# Pg14_FPGA_DDR3.net
KiCad netlist of a schematic drawn in Altium Designer
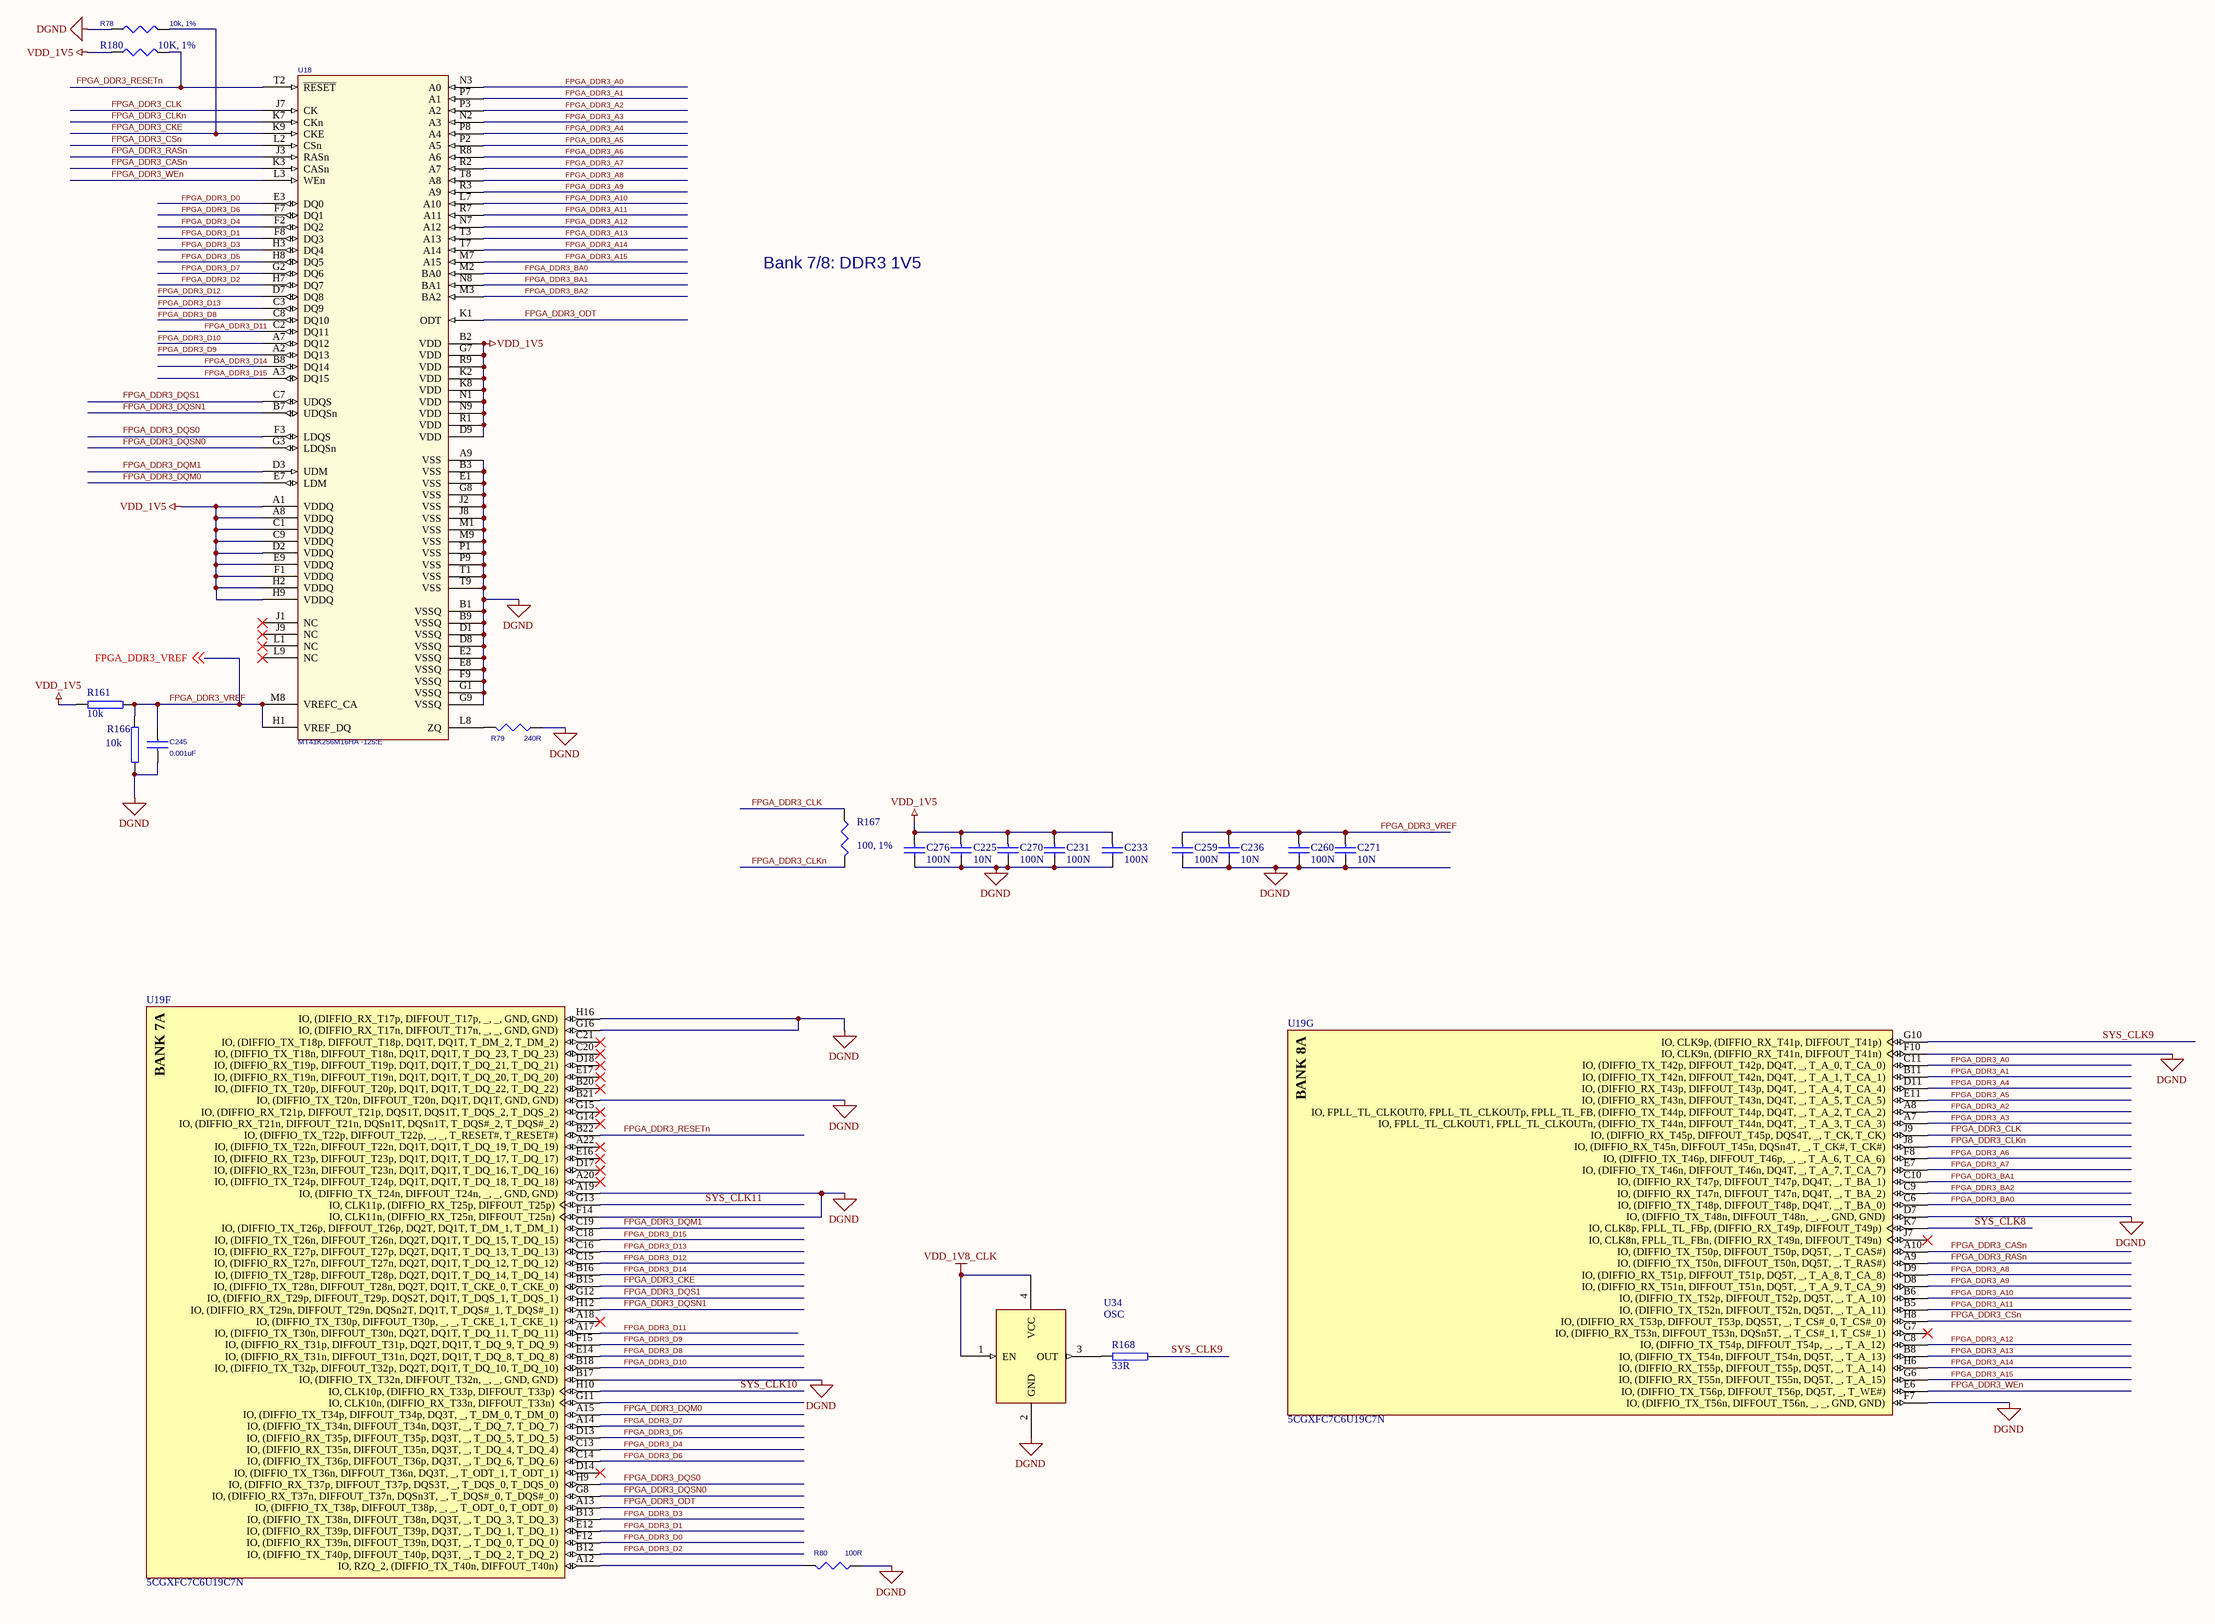
[diagram p0: Pg14_FPGA_DDR3.SchDoc]

(export (version "E")
  (design (tool "Eeschema 10.0.6"))
  (components
    (comp (ref "C225")
      (value "10N")
      (footprint "sc0402")
      (description "NON-POLARISED CAP")
      (libsource (lib "Fireflash_B") (part "CAP"))
    )
    (comp (ref "C231")
      (value "100N")
      (footprint "sc0402")
      (description "NON-POLARISED CAP")
      (libsource (lib "Fireflash_B") (part "CAP"))
    )
    (comp (ref "C233")
      (value "100N")
      (footprint "sc0402")
      (description "NON-POLARISED CAP")
      (libsource (lib "Fireflash_B") (part "CAP"))
    )
    (comp (ref "C236")
      (value "10N")
      (footprint "sc0402")
      (description "NON-POLARISED CAP")
      (libsource (lib "Fireflash_B") (part "CAP"))
    )
    (comp (ref "C245")
      (value "0.001uF")
      (footprint "SM-7351-CAP-0402")
      (fields (field (name "MFR") "AVX") (field (name "TIINTPARTNUMBER") "1C0093"))
      (libsource (lib "*") (part "0.001uFCapacitor50V5%0402"))
    )
    (comp (ref "C259")
      (value "100N")
      (footprint "sc0402")
      (description "NON-POLARISED CAP")
      (libsource (lib "Fireflash_B") (part "CAP"))
    )
    (comp (ref "C260")
      (value "100N")
      (footprint "0603")
      (description "NON-POLARISED CAP")
      (libsource (lib "Fireflash_B") (part "CAP"))
    )
    (comp (ref "C270")
      (value "100N")
      (footprint "sc0402")
      (description "NON-POLARISED CAP")
      (libsource (lib "Fireflash_B") (part "CAP"))
    )
    (comp (ref "C271")
      (value "10N")
      (footprint "sc0402")
      (description "NON-POLARISED CAP")
      (libsource (lib "Fireflash_B") (part "CAP"))
    )
    (comp (ref "C276")
      (value "100N")
      (footprint "sc0402")
      (description "NON-POLARISED CAP")
      (libsource (lib "Fireflash_B") (part "CAP"))
    )
    (comp (ref "R78")
      (value "10k, 1%")
      (footprint "sm-7351-res-0402 - duplicate")
      (description "RES 10K OHM 1/16W 5% 0402 SMD")
      (fields
        (field (name "MANUFACTURER") "Rohm Semiconductor")
        (field (name "MANUFACTURER PART NUMBER") "MCR01MZPJ103")
      )
      (libsource (lib "BEAGLEBONEBLACK_REV A5B") (part "RES_10K_1/16W_1%_0402"))
    )
    (comp (ref "R79")
      (value "240R")
      (footprint "SM-7351-RES-0402")
      (description "Resistor 10Kohm 1/16W 5% 0402")
      (fields (field (name "MFR") "Rohm") (field (name "TIINTPARTNUMBER") "1R0168"))
      (libsource (lib "*") (part "10KOhmResistor1/16W0402"))
    )
    (comp (ref "R80")
      (value "100R")
      (footprint "SM-7351-RES-0402")
      (description "Resistor 10Kohm 1/16W 5% 0402")
      (fields (field (name "MFR") "Rohm") (field (name "TIINTPARTNUMBER") "1R0168"))
      (libsource (lib "*") (part "10KOhmResistor1/16W0402"))
    )
    (comp (ref "R161")
      (value "10k")
      (footprint "0603")
      (description "RESISTOR")
      (libsource (lib "Fireflash_B") (part "RES"))
    )
    (comp (ref "R166")
      (value "10k")
      (footprint "0603")
      (description "RESISTOR")
      (libsource (lib "Fireflash_B") (part "RES"))
    )
    (comp (ref "R167")
      (value "100, 1%")
      (footprint "sc0402")
      (libsource (lib "BEAGLE_C2A_Library") (part "RESISTOR"))
    )
    (comp (ref "R168")
      (value "33R")
      (footprint "sc0402")
      (description "Resistor")
      (libsource (lib "Ibis4") (part "RES"))
    )
    (comp (ref "R180")
      (value "10K, 1%")
      (footprint "sc0402")
      (description "RES 1.50K OHM 1/16W 1% 0402 SMD")
      (fields
        (field (name "MANUFACTURER") "Yageo")
        (field (name "MANUFACTURER PART NUMBER") "RC0402FR-071K5L")
      )
      (libsource (lib "BEAGLEBONEBLACK_REV A5B") (part "RES_10K_1/16W_1%_0402"))
    )
    (comp (ref "U18")
      (value "MT41K256M16HA -125:E")
      (footprint "BGA14X10-96")
      (description "DDR2 SDRAM 2Gb (256Mx8)")
      (fields
        (field (name "MANUFACTURER") "Micron Technology")
        (field (name "MANUFACTURER PART NUMBER") "MT41K256M16HA-125:E")
      )
      (libsource (lib "BEAGLEBONEBLACK_REV A5B") (part "MT41K256M16HA"))
    )
    (comp (ref "U19")
      (value "5CGXFC7C6U19C7N")
      (footprint "ALTR-UBGA484_A-190")
      (fields (field (name "MANUFACTURER") "Altera"))
      (libsource (lib "Altera Cyclone V") (part "5CGXFC7C6U19C7N"))
    )
    (comp (ref "U34")
      (value "OSC")
      (footprint "Osc 3.2x2.5")
      (description "XTAL OSCILLATOR MODULE")
      (libsource (lib "Fireflash_B") (part "OSC"))
    )
  )
  (nets
    (net (code "1") (name "/FPGA_DDR3_A0") (class "Default")
      (node (ref "U18") (pin "N3") (pinfunction "A0_N3") (pintype "input"))
      (node (ref "U19") (pin "C11") (pinfunction "IO,_(DIFFIO_TX_T42p,_DIFFOUT_T42p,_DQ4T,__,_T_A_0,_T_CA_0)_C11") (pintype "bidirectional"))
    )
    (net (code "2") (name "/FPGA_DDR3_A1") (class "Default")
      (node (ref "U18") (pin "P7") (pinfunction "A1_P7") (pintype "input"))
      (node (ref "U19") (pin "B11") (pinfunction "IO,_(DIFFIO_TX_T42n,_DIFFOUT_T42n,_DQ4T,__,_T_A_1,_T_CA_1)_B11") (pintype "bidirectional"))
    )
    (net (code "3") (name "/FPGA_DDR3_A2") (class "Default")
      (node (ref "U18") (pin "P3") (pinfunction "A2_P3") (pintype "input"))
      (node (ref "U19") (pin "A8") (pinfunction "IO,_FPLL_TL_CLKOUT0,_FPLL_TL_CLKOUTp,_FPLL_TL_FB,_(DIFFIO_TX_T44p,_DIFFOUT_T44p,_DQ4T,__,_T_A_2,_T_CA_2)_A8") (pintype "bidirectional"))
    )
    (net (code "4") (name "/FPGA_DDR3_A3") (class "Default")
      (node (ref "U18") (pin "N2") (pinfunction "A3_N2") (pintype "input"))
      (node (ref "U19") (pin "A7") (pinfunction "IO,_FPLL_TL_CLKOUT1,_FPLL_TL_CLKOUTn,_(DIFFIO_TX_T44n,_DIFFOUT_T44n,_DQ4T,__,_T_A_3,_T_CA_3)_A7") (pintype "bidirectional"))
    )
    (net (code "5") (name "/FPGA_DDR3_A4") (class "Default")
      (node (ref "U18") (pin "P8") (pinfunction "A4_P8") (pintype "input"))
      (node (ref "U19") (pin "D11") (pinfunction "IO,_(DIFFIO_RX_T43p,_DIFFOUT_T43p,_DQ4T,__,_T_A_4,_T_CA_4)_D11") (pintype "bidirectional"))
    )
    (net (code "6") (name "/FPGA_DDR3_A5") (class "Default")
      (node (ref "U18") (pin "P2") (pinfunction "A5_P2") (pintype "input"))
      (node (ref "U19") (pin "E11") (pinfunction "IO,_(DIFFIO_RX_T43n,_DIFFOUT_T43n,_DQ4T,__,_T_A_5,_T_CA_5)_E11") (pintype "bidirectional"))
    )
    (net (code "7") (name "/FPGA_DDR3_A6") (class "Default")
      (node (ref "U18") (pin "R8") (pinfunction "A6_R8") (pintype "input"))
      (node (ref "U19") (pin "F8") (pinfunction "IO,_(DIFFIO_TX_T46p,_DIFFOUT_T46p,__,__,_T_A_6,_T_CA_6)_F8") (pintype "bidirectional"))
    )
    (net (code "8") (name "/FPGA_DDR3_A7") (class "Default")
      (node (ref "U18") (pin "R2") (pinfunction "A7_R2") (pintype "input"))
      (node (ref "U19") (pin "E7") (pinfunction "IO,_(DIFFIO_TX_T46n,_DIFFOUT_T46n,_DQ4T,__,_T_A_7,_T_CA_7)_E7") (pintype "bidirectional"))
    )
    (net (code "9") (name "/FPGA_DDR3_A8") (class "Default")
      (node (ref "U18") (pin "T8") (pinfunction "A8_T8") (pintype "input"))
      (node (ref "U19") (pin "D9") (pinfunction "IO,_(DIFFIO_RX_T51p,_DIFFOUT_T51p,_DQ5T,__,_T_A_8,_T_CA_8)_D9") (pintype "bidirectional"))
    )
    (net (code "10") (name "/FPGA_DDR3_A9") (class "Default")
      (node (ref "U18") (pin "R3") (pinfunction "A9_R3") (pintype "input"))
      (node (ref "U19") (pin "D8") (pinfunction "IO,_(DIFFIO_RX_T51n,_DIFFOUT_T51n,_DQ5T,__,_T_A_9,_T_CA_9)_D8") (pintype "bidirectional"))
    )
    (net (code "11") (name "/FPGA_DDR3_A10") (class "Default")
      (node (ref "U18") (pin "L7") (pinfunction "A10_L7") (pintype "input"))
      (node (ref "U19") (pin "B6") (pinfunction "IO,_(DIFFIO_TX_T52p,_DIFFOUT_T52p,_DQ5T,__,_T_A_10)_B6") (pintype "bidirectional"))
    )
    (net (code "12") (name "/FPGA_DDR3_A11") (class "Default")
      (node (ref "U18") (pin "R7") (pinfunction "A11_R7") (pintype "input"))
      (node (ref "U19") (pin "B5") (pinfunction "IO,_(DIFFIO_TX_T52n,_DIFFOUT_T52n,_DQ5T,__,_T_A_11)_B5") (pintype "bidirectional"))
    )
    (net (code "13") (name "/FPGA_DDR3_A12") (class "Default")
      (node (ref "U18") (pin "N7") (pinfunction "A12_N7") (pintype "input"))
      (node (ref "U19") (pin "C8") (pinfunction "IO,_(DIFFIO_TX_T54p,_DIFFOUT_T54p,__,__,_T_A_12)_C8") (pintype "bidirectional"))
    )
    (net (code "14") (name "/FPGA_DDR3_A13") (class "Default")
      (node (ref "U18") (pin "T3") (pinfunction "A13_T3") (pintype "input"))
      (node (ref "U19") (pin "B8") (pinfunction "IO,_(DIFFIO_TX_T54n,_DIFFOUT_T54n,_DQ5T,__,_T_A_13)_B8") (pintype "bidirectional"))
    )
    (net (code "15") (name "/FPGA_DDR3_A14") (class "Default")
      (node (ref "U18") (pin "T7") (pinfunction "A14_T7") (pintype "input"))
      (node (ref "U19") (pin "H6") (pinfunction "IO,_(DIFFIO_RX_T55p,_DIFFOUT_T55p,_DQ5T,__,_T_A_14)_H6") (pintype "bidirectional"))
    )
    (net (code "16") (name "/FPGA_DDR3_A15") (class "Default")
      (node (ref "U18") (pin "M7") (pinfunction "A15_M7") (pintype "input"))
      (node (ref "U19") (pin "G6") (pinfunction "IO,_(DIFFIO_RX_T55n,_DIFFOUT_T55n,_DQ5T,__,_T_A_15)_G6") (pintype "bidirectional"))
    )
    (net (code "17") (name "/FPGA_DDR3_BA0") (class "Default")
      (node (ref "U18") (pin "M2") (pinfunction "BA0_M2") (pintype "input"))
      (node (ref "U19") (pin "C6") (pinfunction "IO,_(DIFFIO_TX_T48p,_DIFFOUT_T48p,_DQ4T,__,_T_BA_0)_C6") (pintype "bidirectional"))
    )
    (net (code "18") (name "/FPGA_DDR3_BA1") (class "Default")
      (node (ref "U18") (pin "N8") (pinfunction "BA1_N8") (pintype "input"))
      (node (ref "U19") (pin "C10") (pinfunction "IO,_(DIFFIO_RX_T47p,_DIFFOUT_T47p,_DQ4T,__,_T_BA_1)_C10") (pintype "bidirectional"))
    )
    (net (code "19") (name "/FPGA_DDR3_BA2") (class "Default")
      (node (ref "U18") (pin "M3") (pinfunction "BA2_M3") (pintype "input"))
      (node (ref "U19") (pin "C9") (pinfunction "IO,_(DIFFIO_RX_T47n,_DIFFOUT_T47n,_DQ4T,__,_T_BA_2)_C9") (pintype "bidirectional"))
    )
    (net (code "20") (name "/FPGA_DDR3_CASn") (class "Default")
      (node (ref "U18") (pin "K3") (pinfunction "CASn_K3") (pintype "input"))
      (node (ref "U19") (pin "A10") (pinfunction "IO,_(DIFFIO_TX_T50p,_DIFFOUT_T50p,_DQ5T,__,_T_CAS#)_A10") (pintype "bidirectional"))
    )
    (net (code "21") (name "/FPGA_DDR3_CKE") (class "Default")
      (node (ref "R78") (pin "2") (pinfunction "2_2") (pintype "passive"))
      (node (ref "U18") (pin "K9") (pinfunction "CKE_K9") (pintype "input"))
      (node (ref "U19") (pin "B15") (pinfunction "IO,_(DIFFIO_TX_T28n,_DIFFOUT_T28n,_DQ2T,_DQ1T,_T_CKE_0,_T_CKE_0)_B15") (pintype "bidirectional"))
    )
    (net (code "22") (name "/FPGA_DDR3_CLK") (class "Default")
      (node (ref "R167") (pin "1") (pinfunction "1_1") (pintype "passive"))
      (node (ref "U18") (pin "J7") (pinfunction "CK_J7") (pintype "input"))
      (node (ref "U19") (pin "J9") (pinfunction "IO,_(DIFFIO_RX_T45p,_DIFFOUT_T45p,_DQS4T,__,_T_CK,_T_CK)_J9") (pintype "bidirectional"))
    )
    (net (code "23") (name "/FPGA_DDR3_CLKn") (class "Default")
      (node (ref "R167") (pin "2") (pinfunction "2_2") (pintype "passive"))
      (node (ref "U18") (pin "K7") (pinfunction "CKn_K7") (pintype "input"))
      (node (ref "U19") (pin "J8") (pinfunction "IO,_(DIFFIO_RX_T45n,_DIFFOUT_T45n,_DQSn4T,__,_T_CK#,_T_CK#)_J8") (pintype "bidirectional"))
    )
    (net (code "24") (name "/FPGA_DDR3_CSn") (class "Default")
      (node (ref "U18") (pin "L2") (pinfunction "CSn_L2") (pintype "input"))
      (node (ref "U19") (pin "H8") (pinfunction "IO,_(DIFFIO_RX_T53p,_DIFFOUT_T53p,_DQS5T,__,_T_CS#_0,_T_CS#_0)_H8") (pintype "bidirectional"))
    )
    (net (code "25") (name "/FPGA_DDR3_D0") (class "Default")
      (node (ref "U18") (pin "E3") (pinfunction "DQ0_E3") (pintype "bidirectional"))
      (node (ref "U19") (pin "F12") (pinfunction "IO,_(DIFFIO_RX_T39n,_DIFFOUT_T39n,_DQ3T,__,_T_DQ_0,_T_DQ_0)_F12") (pintype "bidirectional"))
    )
    (net (code "26") (name "/FPGA_DDR3_D1") (class "Default")
      (node (ref "U18") (pin "F8") (pinfunction "DQ3_F8") (pintype "bidirectional"))
      (node (ref "U19") (pin "E12") (pinfunction "IO,_(DIFFIO_RX_T39p,_DIFFOUT_T39p,_DQ3T,__,_T_DQ_1,_T_DQ_1)_E12") (pintype "bidirectional"))
    )
    (net (code "27") (name "/FPGA_DDR3_D2") (class "Default")
      (node (ref "U18") (pin "H7") (pinfunction "DQ7_H7") (pintype "bidirectional"))
      (node (ref "U19") (pin "B12") (pinfunction "IO,_(DIFFIO_TX_T40p,_DIFFOUT_T40p,_DQ3T,__,_T_DQ_2,_T_DQ_2)_B12") (pintype "bidirectional"))
    )
    (net (code "28") (name "/FPGA_DDR3_D3") (class "Default")
      (node (ref "U18") (pin "H3") (pinfunction "DQ4_H3") (pintype "bidirectional"))
      (node (ref "U19") (pin "B13") (pinfunction "IO,_(DIFFIO_TX_T38n,_DIFFOUT_T38n,_DQ3T,__,_T_DQ_3,_T_DQ_3)_B13") (pintype "bidirectional"))
    )
    (net (code "29") (name "/FPGA_DDR3_D4") (class "Default")
      (node (ref "U18") (pin "F2") (pinfunction "DQ2_F2") (pintype "bidirectional"))
      (node (ref "U19") (pin "C13") (pinfunction "IO,_(DIFFIO_RX_T35n,_DIFFOUT_T35n,_DQ3T,__,_T_DQ_4,_T_DQ_4)_C13") (pintype "bidirectional"))
    )
    (net (code "30") (name "/FPGA_DDR3_D5") (class "Default")
      (node (ref "U18") (pin "H8") (pinfunction "DQ5_H8") (pintype "bidirectional"))
      (node (ref "U19") (pin "D13") (pinfunction "IO,_(DIFFIO_RX_T35p,_DIFFOUT_T35p,_DQ3T,__,_T_DQ_5,_T_DQ_5)_D13") (pintype "bidirectional"))
    )
    (net (code "31") (name "/FPGA_DDR3_D6") (class "Default")
      (node (ref "U18") (pin "F7") (pinfunction "DQ1_F7") (pintype "bidirectional"))
      (node (ref "U19") (pin "C14") (pinfunction "IO,_(DIFFIO_TX_T36p,_DIFFOUT_T36p,_DQ3T,__,_T_DQ_6,_T_DQ_6)_C14") (pintype "bidirectional"))
    )
    (net (code "32") (name "/FPGA_DDR3_D7") (class "Default")
      (node (ref "U18") (pin "G2") (pinfunction "DQ6_G2") (pintype "bidirectional"))
      (node (ref "U19") (pin "A14") (pinfunction "IO,_(DIFFIO_TX_T34n,_DIFFOUT_T34n,_DQ3T,__,_T_DQ_7,_T_DQ_7)_A14") (pintype "bidirectional"))
    )
    (net (code "33") (name "/FPGA_DDR3_D8") (class "Default")
      (node (ref "U18") (pin "C8") (pinfunction "DQ10_C8") (pintype "bidirectional"))
      (node (ref "U19") (pin "E14") (pinfunction "IO,_(DIFFIO_RX_T31n,_DIFFOUT_T31n,_DQ2T,_DQ1T,_T_DQ_8,_T_DQ_8)_E14") (pintype "bidirectional"))
    )
    (net (code "34") (name "/FPGA_DDR3_D9") (class "Default")
      (node (ref "U18") (pin "A2") (pinfunction "DQ13_A2") (pintype "bidirectional"))
      (node (ref "U19") (pin "F15") (pinfunction "IO,_(DIFFIO_RX_T31p,_DIFFOUT_T31p,_DQ2T,_DQ1T,_T_DQ_9,_T_DQ_9)_F15") (pintype "bidirectional"))
    )
    (net (code "35") (name "/FPGA_DDR3_D10") (class "Default")
      (node (ref "U18") (pin "A7") (pinfunction "DQ12_A7") (pintype "bidirectional"))
      (node (ref "U19") (pin "B18") (pinfunction "IO,_(DIFFIO_TX_T32p,_DIFFOUT_T32p,_DQ2T,_DQ1T,_T_DQ_10,_T_DQ_10)_B18") (pintype "bidirectional"))
    )
    (net (code "36") (name "/FPGA_DDR3_D11") (class "Default")
      (node (ref "U18") (pin "C2") (pinfunction "DQ11_C2") (pintype "bidirectional"))
      (node (ref "U19") (pin "A17") (pinfunction "IO,_(DIFFIO_TX_T30n,_DIFFOUT_T30n,_DQ2T,_DQ1T,_T_DQ_11,_T_DQ_11)_A17") (pintype "bidirectional"))
    )
    (net (code "37") (name "/FPGA_DDR3_D12") (class "Default")
      (node (ref "U18") (pin "D7") (pinfunction "DQ8_D7") (pintype "bidirectional"))
      (node (ref "U19") (pin "C15") (pinfunction "IO,_(DIFFIO_RX_T27n,_DIFFOUT_T27n,_DQ2T,_DQ1T,_T_DQ_12,_T_DQ_12)_C15") (pintype "bidirectional"))
    )
    (net (code "38") (name "/FPGA_DDR3_D13") (class "Default")
      (node (ref "U18") (pin "C3") (pinfunction "DQ9_C3") (pintype "bidirectional"))
      (node (ref "U19") (pin "C16") (pinfunction "IO,_(DIFFIO_RX_T27p,_DIFFOUT_T27p,_DQ2T,_DQ1T,_T_DQ_13,_T_DQ_13)_C16") (pintype "bidirectional"))
    )
    (net (code "39") (name "/FPGA_DDR3_D14") (class "Default")
      (node (ref "U18") (pin "B8") (pinfunction "DQ14_B8") (pintype "bidirectional"))
      (node (ref "U19") (pin "B16") (pinfunction "IO,_(DIFFIO_TX_T28p,_DIFFOUT_T28p,_DQ2T,_DQ1T,_T_DQ_14,_T_DQ_14)_B16") (pintype "bidirectional"))
    )
    (net (code "40") (name "/FPGA_DDR3_D15") (class "Default")
      (node (ref "U18") (pin "A3") (pinfunction "DQ15_A3") (pintype "bidirectional"))
      (node (ref "U19") (pin "C18") (pinfunction "IO,_(DIFFIO_TX_T26n,_DIFFOUT_T26n,_DQ2T,_DQ1T,_T_DQ_15,_T_DQ_15)_C18") (pintype "bidirectional"))
    )
    (net (code "41") (name "/FPGA_DDR3_DQM0") (class "Default")
      (node (ref "U18") (pin "E7") (pinfunction "LDM_E7") (pintype "bidirectional"))
      (node (ref "U19") (pin "A15") (pinfunction "IO,_(DIFFIO_TX_T34p,_DIFFOUT_T34p,_DQ3T,__,_T_DM_0,_T_DM_0)_A15") (pintype "bidirectional"))
    )
    (net (code "42") (name "/FPGA_DDR3_DQM1") (class "Default")
      (node (ref "U18") (pin "D3") (pinfunction "UDM_D3") (pintype "input"))
      (node (ref "U19") (pin "C19") (pinfunction "IO,_(DIFFIO_TX_T26p,_DIFFOUT_T26p,_DQ2T,_DQ1T,_T_DM_1,_T_DM_1)_C19") (pintype "bidirectional"))
    )
    (net (code "43") (name "/FPGA_DDR3_DQS0") (class "Default")
      (node (ref "U18") (pin "F3") (pinfunction "LDQS_F3") (pintype "bidirectional"))
      (node (ref "U19") (pin "H9") (pinfunction "IO,_(DIFFIO_RX_T37p,_DIFFOUT_T37p,_DQS3T,__,_T_DQS_0,_T_DQS_0)_H9") (pintype "bidirectional"))
    )
    (net (code "44") (name "/FPGA_DDR3_DQS1") (class "Default")
      (node (ref "U18") (pin "C7") (pinfunction "UDQS_C7") (pintype "bidirectional"))
      (node (ref "U19") (pin "G12") (pinfunction "IO,_(DIFFIO_RX_T29p,_DIFFOUT_T29p,_DQS2T,_DQ1T,_T_DQS_1,_T_DQS_1)_G12") (pintype "bidirectional"))
    )
    (net (code "45") (name "/FPGA_DDR3_DQSN0") (class "Default")
      (node (ref "U18") (pin "G3") (pinfunction "LDQSn_G3") (pintype "bidirectional"))
      (node (ref "U19") (pin "G8") (pinfunction "IO,_(DIFFIO_RX_T37n,_DIFFOUT_T37n,_DQSn3T,__,_T_DQS#_0,_T_DQS#_0)_G8") (pintype "bidirectional"))
    )
    (net (code "46") (name "/FPGA_DDR3_DQSN1") (class "Default")
      (node (ref "U18") (pin "B7") (pinfunction "UDQSn_B7") (pintype "bidirectional"))
      (node (ref "U19") (pin "H12") (pinfunction "IO,_(DIFFIO_RX_T29n,_DIFFOUT_T29n,_DQSn2T,_DQ1T,_T_DQS#_1,_T_DQS#_1)_H12") (pintype "bidirectional"))
    )
    (net (code "47") (name "/FPGA_DDR3_ODT") (class "Default")
      (node (ref "U18") (pin "K1") (pinfunction "ODT_K1") (pintype "input"))
      (node (ref "U19") (pin "A13") (pinfunction "IO,_(DIFFIO_TX_T38p,_DIFFOUT_T38p,__,__,_T_ODT_0,_T_ODT_0)_A13") (pintype "bidirectional"))
    )
    (net (code "48") (name "/FPGA_DDR3_RASn") (class "Default")
      (node (ref "U18") (pin "J3") (pinfunction "RASn_J3") (pintype "input"))
      (node (ref "U19") (pin "A9") (pinfunction "IO,_(DIFFIO_TX_T50n,_DIFFOUT_T50n,_DQ5T,__,_T_RAS#)_A9") (pintype "bidirectional"))
    )
    (net (code "49") (name "/FPGA_DDR3_RESETn") (class "Default")
      (node (ref "R180") (pin "2") (pinfunction "2_2") (pintype "passive"))
      (node (ref "U18") (pin "T2") (pinfunction "~{RESET}_T2") (pintype "input"))
      (node (ref "U19") (pin "B22") (pinfunction "IO,_(DIFFIO_TX_T22p,_DIFFOUT_T22p,__,__,_T_RESET#,_T_RESET#)_B22") (pintype "bidirectional"))
    )
    (net (code "50") (name "/FPGA_DDR3_WEn") (class "Default")
      (node (ref "U18") (pin "L3") (pinfunction "WEn_L3") (pintype "input"))
      (node (ref "U19") (pin "E6") (pinfunction "IO,_(DIFFIO_TX_T56p,_DIFFOUT_T56p,_DQ5T,__,_T_WE#)_E6") (pintype "bidirectional"))
    )
    (net (code "51") (name "/SYS_CLK8") (class "Default")
      (node (ref "U19") (pin "K7") (pinfunction "IO,_CLK8p,_FPLL_TL_FBp,_(DIFFIO_RX_T49p,_DIFFOUT_T49p)_K7") (pintype "bidirectional"))
    )
    (net (code "52") (name "/SYS_CLK9") (class "Default")
      (node (ref "R168") (pin "2") (pintype "passive"))
      (node (ref "U19") (pin "G10") (pinfunction "IO,_CLK9p,_(DIFFIO_RX_T41p,_DIFFOUT_T41p)_G10") (pintype "bidirectional"))
    )
    (net (code "53") (name "/SYS_CLK10") (class "Default")
      (node (ref "U19") (pin "H10") (pinfunction "IO,_CLK10p,_(DIFFIO_RX_T33p,_DIFFOUT_T33p)_H10") (pintype "bidirectional"))
    )
    (net (code "54") (name "/SYS_CLK11") (class "Default")
      (node (ref "U19") (pin "G13") (pinfunction "IO,_CLK11p,_(DIFFIO_RX_T25p,_DIFFOUT_T25p)_G13") (pintype "bidirectional"))
    )
    (net (code "55") (name "DGND") (class "Default")
      (node (ref "C225") (pin "2") (pintype "passive"))
      (node (ref "C231") (pin "2") (pintype "passive"))
      (node (ref "C233") (pin "2") (pintype "passive"))
      (node (ref "C236") (pin "2") (pintype "passive"))
      (node (ref "C245") (pin "2") (pinfunction "2_2") (pintype "passive"))
      (node (ref "C259") (pin "2") (pintype "passive"))
      (node (ref "C260") (pin "2") (pintype "passive"))
      (node (ref "C270") (pin "2") (pintype "passive"))
      (node (ref "C271") (pin "2") (pintype "passive"))
      (node (ref "C276") (pin "2") (pintype "passive"))
      (node (ref "R166") (pin "2") (pintype "passive"))
      (node (ref "R78") (pin "1") (pinfunction "1_1") (pintype "passive"))
      (node (ref "R79") (pin "2") (pinfunction "P2_2") (pintype "passive"))
      (node (ref "R80") (pin "2") (pinfunction "P2_2") (pintype "passive"))
      (node (ref "U18") (pin "A9") (pinfunction "VSS_A9") (pintype "power_in"))
      (node (ref "U18") (pin "B1") (pinfunction "VSSQ_B1") (pintype "power_in"))
      (node (ref "U18") (pin "B3") (pinfunction "VSS_B3") (pintype "power_in"))
      (node (ref "U18") (pin "B9") (pinfunction "VSSQ_B9") (pintype "power_in"))
      (node (ref "U18") (pin "D1") (pinfunction "VSSQ_D1") (pintype "power_in"))
      (node (ref "U18") (pin "D8") (pinfunction "VSSQ_D8") (pintype "power_in"))
      (node (ref "U18") (pin "E1") (pinfunction "VSS_E1") (pintype "power_in"))
      (node (ref "U18") (pin "E2") (pinfunction "VSSQ_E2") (pintype "power_in"))
      (node (ref "U18") (pin "E8") (pinfunction "VSSQ_E8") (pintype "power_in"))
      (node (ref "U18") (pin "F9") (pinfunction "VSSQ_F9") (pintype "power_in"))
      (node (ref "U18") (pin "G1") (pinfunction "VSSQ_G1") (pintype "power_in"))
      (node (ref "U18") (pin "G8") (pinfunction "VSS_G8") (pintype "power_in"))
      (node (ref "U18") (pin "G9") (pinfunction "VSSQ_G9") (pintype "power_in"))
      (node (ref "U18") (pin "J2") (pinfunction "VSS_J2") (pintype "power_in"))
      (node (ref "U18") (pin "J8") (pinfunction "VSS_J8") (pintype "power_in"))
      (node (ref "U18") (pin "M1") (pinfunction "VSS_M1") (pintype "power_in"))
      (node (ref "U18") (pin "M9") (pinfunction "VSS_M9") (pintype "power_in"))
      (node (ref "U18") (pin "P1") (pinfunction "VSS_P1") (pintype "power_in"))
      (node (ref "U18") (pin "P9") (pinfunction "VSS_P9") (pintype "power_in"))
      (node (ref "U18") (pin "T1") (pinfunction "VSS_T1") (pintype "power_in"))
      (node (ref "U18") (pin "T9") (pinfunction "VSS_T9") (pintype "power_in"))
      (node (ref "U19") (pin "A19") (pinfunction "IO,_(DIFFIO_TX_T24n,_DIFFOUT_T24n,__,__,_GND,_GND)_A19") (pintype "bidirectional"))
      (node (ref "U19") (pin "B17") (pinfunction "IO,_(DIFFIO_TX_T32n,_DIFFOUT_T32n,__,__,_GND,_GND)_B17") (pintype "bidirectional"))
      (node (ref "U19") (pin "B21") (pinfunction "IO,_(DIFFIO_TX_T20n,_DIFFOUT_T20n,_DQ1T,_DQ1T,_GND,_GND)_B21") (pintype "bidirectional"))
      (node (ref "U19") (pin "D7") (pinfunction "IO,_(DIFFIO_TX_T48n,_DIFFOUT_T48n,__,__,_GND,_GND)_D7") (pintype "bidirectional"))
      (node (ref "U19") (pin "F10") (pinfunction "IO,_CLK9n,_(DIFFIO_RX_T41n,_DIFFOUT_T41n)_F10") (pintype "bidirectional"))
      (node (ref "U19") (pin "F14") (pinfunction "IO,_CLK11n,_(DIFFIO_RX_T25n,_DIFFOUT_T25n)_F14") (pintype "bidirectional"))
      (node (ref "U19") (pin "F7") (pinfunction "IO,_(DIFFIO_TX_T56n,_DIFFOUT_T56n,__,__,_GND,_GND)_F7") (pintype "bidirectional"))
      (node (ref "U19") (pin "G16") (pinfunction "IO,_(DIFFIO_RX_T17n,_DIFFOUT_T17n,__,__,_GND,_GND)_G16") (pintype "bidirectional"))
      (node (ref "U19") (pin "H16") (pinfunction "IO,_(DIFFIO_RX_T17p,_DIFFOUT_T17p,__,__,_GND,_GND)_H16") (pintype "bidirectional"))
      (node (ref "U34") (pin "2") (pinfunction "GND_2") (pintype "power_in"))
    )
    (net (code "56") (name "FPGA_DDR3_VREF") (class "Default")
      (node (ref "C236") (pin "1") (pintype "passive"))
      (node (ref "C245") (pin "1") (pinfunction "1_1") (pintype "passive"))
      (node (ref "C259") (pin "1") (pintype "passive"))
      (node (ref "C260") (pin "1") (pintype "passive"))
      (node (ref "C271") (pin "1") (pintype "passive"))
      (node (ref "R161") (pin "2") (pintype "passive"))
      (node (ref "R166") (pin "1") (pintype "passive"))
      (node (ref "U18") (pin "H1") (pinfunction "VREF_DQ_H1") (pintype "passive"))
      (node (ref "U18") (pin "M8") (pinfunction "VREFC_CA_M8") (pintype "power_in"))
    )
    (net (code "57") (name "Net-(R79-P1)") (class "Default")
      (node (ref "R79") (pin "1") (pinfunction "P1_1") (pintype "passive"))
      (node (ref "U18") (pin "L8") (pinfunction "ZQ_L8") (pintype "passive"))
    )
    (net (code "58") (name "Net-(R80-P1)") (class "Default")
      (node (ref "R80") (pin "1") (pinfunction "P1_1") (pintype "passive"))
      (node (ref "U19") (pin "A12") (pinfunction "IO,_RZQ_2,_(DIFFIO_TX_T40n,_DIFFOUT_T40n)_A12") (pintype "bidirectional"))
    )
    (net (code "59") (name "Net-(U34-OUT)") (class "Default")
      (node (ref "R168") (pin "1") (pintype "passive"))
      (node (ref "U34") (pin "3") (pinfunction "OUT_3") (pintype "output"))
    )
    (net (code "60") (name "VDD_1V5") (class "Default")
      (node (ref "C225") (pin "1") (pintype "passive"))
      (node (ref "C231") (pin "1") (pintype "passive"))
      (node (ref "C233") (pin "1") (pintype "passive"))
      (node (ref "C270") (pin "1") (pintype "passive"))
      (node (ref "C276") (pin "1") (pintype "passive"))
      (node (ref "R161") (pin "1") (pintype "passive"))
      (node (ref "R180") (pin "1") (pinfunction "1_1") (pintype "passive"))
      (node (ref "U18") (pin "A1") (pinfunction "VDDQ_A1") (pintype "power_in"))
      (node (ref "U18") (pin "A8") (pinfunction "VDDQ_A8") (pintype "power_in"))
      (node (ref "U18") (pin "B2") (pinfunction "VDD_B2") (pintype "power_in"))
      (node (ref "U18") (pin "C1") (pinfunction "VDDQ_C1") (pintype "power_in"))
      (node (ref "U18") (pin "C9") (pinfunction "VDDQ_C9") (pintype "power_in"))
      (node (ref "U18") (pin "D2") (pinfunction "VDDQ_D2") (pintype "power_in"))
      (node (ref "U18") (pin "D9") (pinfunction "VDD_D9") (pintype "power_in"))
      (node (ref "U18") (pin "E9") (pinfunction "VDDQ_E9") (pintype "power_in"))
      (node (ref "U18") (pin "F1") (pinfunction "VDDQ_F1") (pintype "power_in"))
      (node (ref "U18") (pin "G7") (pinfunction "VDD_G7") (pintype "power_in"))
      (node (ref "U18") (pin "H2") (pinfunction "VDDQ_H2") (pintype "power_in"))
      (node (ref "U18") (pin "H9") (pinfunction "VDDQ_H9") (pintype "power_in"))
      (node (ref "U18") (pin "K2") (pinfunction "VDD_K2") (pintype "power_in"))
      (node (ref "U18") (pin "K8") (pinfunction "VDD_K8") (pintype "power_in"))
      (node (ref "U18") (pin "N1") (pinfunction "VDD_N1") (pintype "power_in"))
      (node (ref "U18") (pin "N9") (pinfunction "VDD_N9") (pintype "power_in"))
      (node (ref "U18") (pin "R1") (pinfunction "VDD_R1") (pintype "power_in"))
      (node (ref "U18") (pin "R9") (pinfunction "VDD_R9") (pintype "power_in"))
    )
    (net (code "61") (name "VDD_1V8_CLK") (class "Default")
      (node (ref "U34") (pin "1") (pinfunction "EN_1") (pintype "input"))
      (node (ref "U34") (pin "4") (pinfunction "VCC_4") (pintype "power_in"))
    )
    (net (code "62") (name "unconnected-(U18-NC-PadJ1)") (class "Default")
      (node (ref "U18") (pin "J1") (pinfunction "NC_J1") (pintype "passive+no_connect"))
    )
    (net (code "63") (name "unconnected-(U18-NC-PadJ9)") (class "Default")
      (node (ref "U18") (pin "J9") (pinfunction "NC_J9") (pintype "passive+no_connect"))
    )
    (net (code "64") (name "unconnected-(U18-NC-PadL1)") (class "Default")
      (node (ref "U18") (pin "L1") (pinfunction "NC_L1") (pintype "power_in+no_connect"))
    )
    (net (code "65") (name "unconnected-(U18-NC-PadL9)") (class "Default")
      (node (ref "U18") (pin "L9") (pinfunction "NC_L9") (pintype "power_in+no_connect"))
    )
    (net (code "66") (name "unconnected-(U19F-IO,_(DIFFIO_RX_T19n,_DIFFOUT_T19n,_DQ1T,_DQ1T,_T_DQ_20,_T_DQ_20)-PadE17)") (class "Default")
      (node (ref "U19") (pin "E17") (pinfunction "IO,_(DIFFIO_RX_T19n,_DIFFOUT_T19n,_DQ1T,_DQ1T,_T_DQ_20,_T_DQ_20)_E17") (pintype "bidirectional+no_connect"))
    )
    (net (code "67") (name "unconnected-(U19F-IO,_(DIFFIO_RX_T19p,_DIFFOUT_T19p,_DQ1T,_DQ1T,_T_DQ_21,_T_DQ_21)-PadD18)") (class "Default")
      (node (ref "U19") (pin "D18") (pinfunction "IO,_(DIFFIO_RX_T19p,_DIFFOUT_T19p,_DQ1T,_DQ1T,_T_DQ_21,_T_DQ_21)_D18") (pintype "bidirectional+no_connect"))
    )
    (net (code "68") (name "unconnected-(U19F-IO,_(DIFFIO_RX_T21n,_DIFFOUT_T21n,_DQSn1T,_DQSn1T,_T_DQS#_2,_T_DQS#_2)-PadG14)") (class "Default")
      (node (ref "U19") (pin "G14") (pinfunction "IO,_(DIFFIO_RX_T21n,_DIFFOUT_T21n,_DQSn1T,_DQSn1T,_T_DQS#_2,_T_DQS#_2)_G14") (pintype "bidirectional+no_connect"))
    )
    (net (code "69") (name "unconnected-(U19F-IO,_(DIFFIO_RX_T21p,_DIFFOUT_T21p,_DQS1T,_DQS1T,_T_DQS_2,_T_DQS_2)-PadG15)") (class "Default")
      (node (ref "U19") (pin "G15") (pinfunction "IO,_(DIFFIO_RX_T21p,_DIFFOUT_T21p,_DQS1T,_DQS1T,_T_DQS_2,_T_DQS_2)_G15") (pintype "bidirectional+no_connect"))
    )
    (net (code "70") (name "unconnected-(U19F-IO,_(DIFFIO_RX_T23n,_DIFFOUT_T23n,_DQ1T,_DQ1T,_T_DQ_16,_T_DQ_16)-PadD17)") (class "Default")
      (node (ref "U19") (pin "D17") (pinfunction "IO,_(DIFFIO_RX_T23n,_DIFFOUT_T23n,_DQ1T,_DQ1T,_T_DQ_16,_T_DQ_16)_D17") (pintype "bidirectional+no_connect"))
    )
    (net (code "71") (name "unconnected-(U19F-IO,_(DIFFIO_RX_T23p,_DIFFOUT_T23p,_DQ1T,_DQ1T,_T_DQ_17,_T_DQ_17)-PadE16)") (class "Default")
      (node (ref "U19") (pin "E16") (pinfunction "IO,_(DIFFIO_RX_T23p,_DIFFOUT_T23p,_DQ1T,_DQ1T,_T_DQ_17,_T_DQ_17)_E16") (pintype "bidirectional+no_connect"))
    )
    (net (code "72") (name "unconnected-(U19F-IO,_(DIFFIO_TX_T18n,_DIFFOUT_T18n,_DQ1T,_DQ1T,_T_DQ_23,_T_DQ_23)-PadC20)") (class "Default")
      (node (ref "U19") (pin "C20") (pinfunction "IO,_(DIFFIO_TX_T18n,_DIFFOUT_T18n,_DQ1T,_DQ1T,_T_DQ_23,_T_DQ_23)_C20") (pintype "bidirectional+no_connect"))
    )
    (net (code "73") (name "unconnected-(U19F-IO,_(DIFFIO_TX_T18p,_DIFFOUT_T18p,_DQ1T,_DQ1T,_T_DM_2,_T_DM_2)-PadC21)") (class "Default")
      (node (ref "U19") (pin "C21") (pinfunction "IO,_(DIFFIO_TX_T18p,_DIFFOUT_T18p,_DQ1T,_DQ1T,_T_DM_2,_T_DM_2)_C21") (pintype "bidirectional+no_connect"))
    )
    (net (code "74") (name "unconnected-(U19F-IO,_(DIFFIO_TX_T20p,_DIFFOUT_T20p,_DQ1T,_DQ1T,_T_DQ_22,_T_DQ_22)-PadB20)") (class "Default")
      (node (ref "U19") (pin "B20") (pinfunction "IO,_(DIFFIO_TX_T20p,_DIFFOUT_T20p,_DQ1T,_DQ1T,_T_DQ_22,_T_DQ_22)_B20") (pintype "bidirectional+no_connect"))
    )
    (net (code "75") (name "unconnected-(U19F-IO,_(DIFFIO_TX_T22n,_DIFFOUT_T22n,_DQ1T,_DQ1T,_T_DQ_19,_T_DQ_19)-PadA22)") (class "Default")
      (node (ref "U19") (pin "A22") (pinfunction "IO,_(DIFFIO_TX_T22n,_DIFFOUT_T22n,_DQ1T,_DQ1T,_T_DQ_19,_T_DQ_19)_A22") (pintype "bidirectional+no_connect"))
    )
    (net (code "76") (name "unconnected-(U19F-IO,_(DIFFIO_TX_T24p,_DIFFOUT_T24p,_DQ1T,_DQ1T,_T_DQ_18,_T_DQ_18)-PadA20)") (class "Default")
      (node (ref "U19") (pin "A20") (pinfunction "IO,_(DIFFIO_TX_T24p,_DIFFOUT_T24p,_DQ1T,_DQ1T,_T_DQ_18,_T_DQ_18)_A20") (pintype "bidirectional+no_connect"))
    )
    (net (code "77") (name "unconnected-(U19F-IO,_(DIFFIO_TX_T30p,_DIFFOUT_T30p,__,__,_T_CKE_1,_T_CKE_1)-PadA18)") (class "Default")
      (node (ref "U19") (pin "A18") (pinfunction "IO,_(DIFFIO_TX_T30p,_DIFFOUT_T30p,__,__,_T_CKE_1,_T_CKE_1)_A18") (pintype "bidirectional+no_connect"))
    )
    (net (code "78") (name "unconnected-(U19F-IO,_(DIFFIO_TX_T36n,_DIFFOUT_T36n,_DQ3T,__,_T_ODT_1,_T_ODT_1)-PadD14)") (class "Default")
      (node (ref "U19") (pin "D14") (pinfunction "IO,_(DIFFIO_TX_T36n,_DIFFOUT_T36n,_DQ3T,__,_T_ODT_1,_T_ODT_1)_D14") (pintype "bidirectional+no_connect"))
    )
    (net (code "79") (name "unconnected-(U19F-IO,_CLK10n,_(DIFFIO_RX_T33n,_DIFFOUT_T33n)-PadG11)") (class "Default")
      (node (ref "U19") (pin "G11") (pinfunction "IO,_CLK10n,_(DIFFIO_RX_T33n,_DIFFOUT_T33n)_G11") (pintype "bidirectional"))
    )
    (net (code "80") (name "unconnected-(U19G-IO,_(DIFFIO_RX_T53n,_DIFFOUT_T53n,_DQSn5T,__,_T_CS#_1,_T_CS#_1)-PadG7)") (class "Default")
      (node (ref "U19") (pin "G7") (pinfunction "IO,_(DIFFIO_RX_T53n,_DIFFOUT_T53n,_DQSn5T,__,_T_CS#_1,_T_CS#_1)_G7") (pintype "bidirectional+no_connect"))
    )
    (net (code "81") (name "unconnected-(U19G-IO,_CLK8n,_FPLL_TL_FBn,_(DIFFIO_RX_T49n,_DIFFOUT_T49n)-PadJ7)") (class "Default")
      (node (ref "U19") (pin "J7") (pinfunction "IO,_CLK8n,_FPLL_TL_FBn,_(DIFFIO_RX_T49n,_DIFFOUT_T49n)_J7") (pintype "bidirectional+no_connect"))
    )
  )
)
